# SOS_receiver.net
KiCad netlist of a schematic drawn in EasyEDA
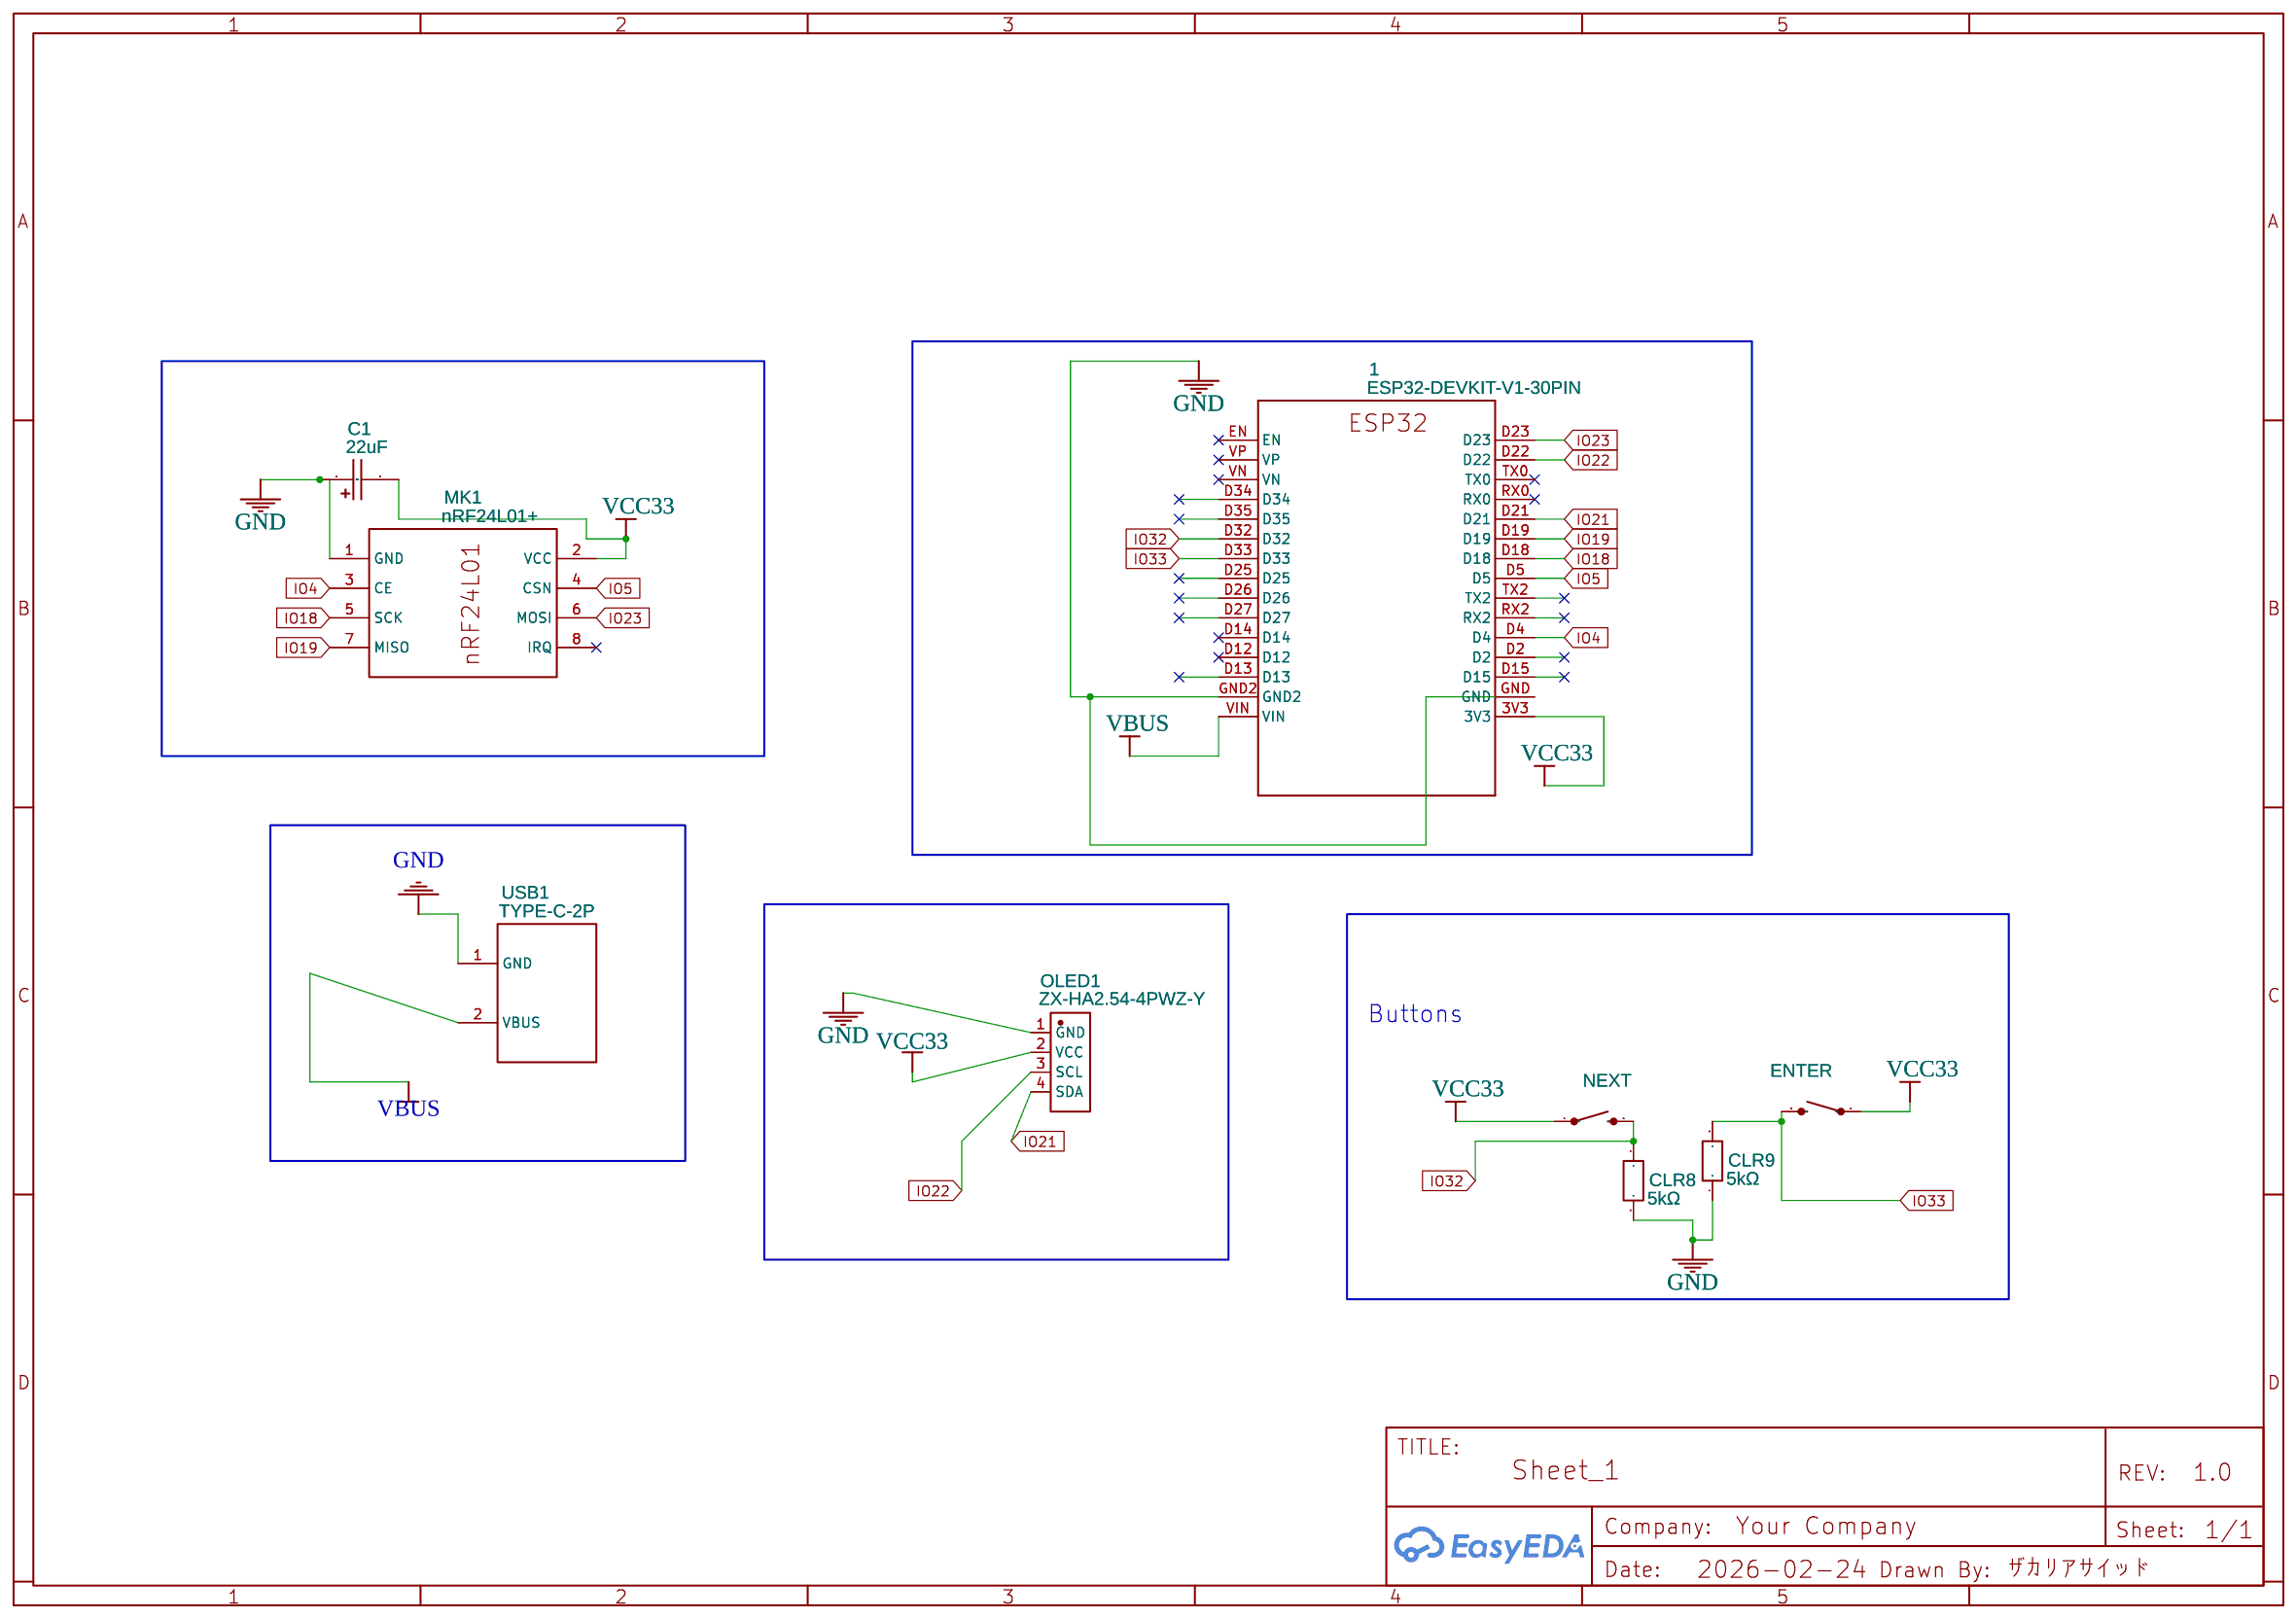
[diagram p0: schematic sheet]

(export (version "E")
  (design (tool "Eeschema 10.0.6"))
  (components
    (comp (ref "1") (value "ESP32-DEVKIT-V1-30PIN") (libsource (lib "") (part "ESP32-DEVKIT-V1-30PIN")))
    (comp (ref "C1")
      (value "22uF")
      (fields (field (name "Manufacturer Part") "UES1V220MPM1TD") (field (name "Manufacturer") "Nichicon"))
      (libsource (lib "") (part "22uF_16V"))
    )
    (comp (ref "CLR8") (value "5kΩ") (libsource (lib "") (part "R_AXIAL-0.4_EU_1")))
    (comp (ref "CLR9") (value "5kΩ") (libsource (lib "") (part "R_AXIAL-0.4_EU")))
    (comp (ref "ENTER") (value "SWITCHES_PTH_EZ") (libsource (lib "") (part "SWITCHES_PTH_EZ_1")))
    (comp (ref "MK1") (value "nRF24L01+") (libsource (lib "") (part "nRF24L01+")))
    (comp (ref "NEXT") (value "SWITCHES_PTH_EZ") (libsource (lib "") (part "SWITCHES_PTH_EZ")))
    (comp (ref "OLED1")
      (value "ZX-HA2.54-4PWZ-Y")
      (fields (field (name "Manufacturer") "Megastar(兆星)"))
      (libsource (lib "") (part "ZX-HA2.54-4PWZ-Y"))
    )
    (comp (ref "USB1") (value "TYPE-C-2P") (libsource (lib "") (part "TYPE-C-2P")))
  )
  (nets
    (net (code "1") (name "GND") (class "Default")
      (node (ref "1") (pin "GND") (pinfunction "GND_GND") (pintype "unspecified"))
      (node (ref "1") (pin "GND2") (pinfunction "GND2_GND2") (pintype "unspecified"))
      (node (ref "C1") (pin "1") (pinfunction "1_1") (pintype "unspecified"))
      (node (ref "CLR8") (pin "2") (pinfunction "2_2") (pintype "unspecified"))
      (node (ref "CLR9") (pin "1") (pinfunction "1_1") (pintype "unspecified"))
      (node (ref "MK1") (pin "1") (pinfunction "GND_1") (pintype "unspecified"))
      (node (ref "OLED1") (pin "1") (pinfunction "GND_1") (pintype "unspecified"))
      (node (ref "USB1") (pin "1") (pinfunction "GND_1") (pintype "unspecified"))
    )
    (net (code "2") (name "IO4") (class "Default")
      (node (ref "1") (pin "D4") (pinfunction "D4_D4") (pintype "unspecified"))
      (node (ref "MK1") (pin "3") (pinfunction "CE_3") (pintype "unspecified"))
    )
    (net (code "3") (name "IO5") (class "Default")
      (node (ref "1") (pin "D5") (pinfunction "D5_D5") (pintype "unspecified"))
      (node (ref "MK1") (pin "4") (pinfunction "CSN_4") (pintype "unspecified"))
    )
    (net (code "4") (name "IO18") (class "Default")
      (node (ref "1") (pin "D18") (pinfunction "D18_D18") (pintype "unspecified"))
      (node (ref "MK1") (pin "5") (pinfunction "SCK_5") (pintype "unspecified"))
    )
    (net (code "5") (name "IO19") (class "Default")
      (node (ref "1") (pin "D19") (pinfunction "D19_D19") (pintype "unspecified"))
      (node (ref "MK1") (pin "7") (pinfunction "MISO_7") (pintype "unspecified"))
    )
    (net (code "6") (name "IO21") (class "Default")
      (node (ref "1") (pin "D21") (pinfunction "D21_D21") (pintype "unspecified"))
      (node (ref "OLED1") (pin "4") (pinfunction "SDA_4") (pintype "unspecified"))
    )
    (net (code "7") (name "IO22") (class "Default")
      (node (ref "1") (pin "D22") (pinfunction "D22_D22") (pintype "unspecified"))
      (node (ref "OLED1") (pin "3") (pinfunction "SCL_3") (pintype "unspecified"))
    )
    (net (code "8") (name "IO23") (class "Default")
      (node (ref "1") (pin "D23") (pinfunction "D23_D23") (pintype "unspecified"))
      (node (ref "MK1") (pin "6") (pinfunction "MOSI_6") (pintype "unspecified"))
    )
    (net (code "9") (name "IO32") (class "Default")
      (node (ref "1") (pin "D32") (pinfunction "D32_D32") (pintype "unspecified"))
      (node (ref "CLR8") (pin "1") (pinfunction "1_1") (pintype "unspecified"))
      (node (ref "NEXT") (pin "3") (pinfunction "2_3") (pintype "unspecified"))
    )
    (net (code "10") (name "IO33") (class "Default")
      (node (ref "1") (pin "D33") (pinfunction "D33_D33") (pintype "unspecified"))
      (node (ref "CLR9") (pin "2") (pinfunction "2_2") (pintype "unspecified"))
      (node (ref "ENTER") (pin "3") (pinfunction "2_3") (pintype "unspecified"))
    )
    (net (code "11") (name "VBUS") (class "Default")
      (node (ref "1") (pin "VIN") (pinfunction "VIN_VIN") (pintype "unspecified"))
      (node (ref "USB1") (pin "2") (pinfunction "VBUS_2") (pintype "unspecified"))
    )
    (net (code "12") (name "VCC33") (class "Default")
      (node (ref "1") (pin "3V3") (pinfunction "3V3_3V3") (pintype "unspecified"))
      (node (ref "C1") (pin "2") (pinfunction "2_2") (pintype "unspecified"))
      (node (ref "ENTER") (pin "1") (pinfunction "1_1") (pintype "unspecified"))
      (node (ref "MK1") (pin "2") (pinfunction "VCC_2") (pintype "unspecified"))
      (node (ref "NEXT") (pin "1") (pinfunction "1_1") (pintype "unspecified"))
      (node (ref "OLED1") (pin "2") (pinfunction "VCC_2") (pintype "unspecified"))
    )
    (net (code "13") (name "unconnected-(1-PadD2)") (class "Default")
      (node (ref "1") (pin "D2") (pinfunction "D2_D2") (pintype "unspecified+no_connect"))
    )
    (net (code "14") (name "unconnected-(1-PadD12)") (class "Default")
      (node (ref "1") (pin "D12") (pinfunction "D12_D12") (pintype "unspecified+no_connect"))
    )
    (net (code "15") (name "unconnected-(1-PadD13)") (class "Default")
      (node (ref "1") (pin "D13") (pinfunction "D13_D13") (pintype "unspecified+no_connect"))
    )
    (net (code "16") (name "unconnected-(1-PadD14)") (class "Default")
      (node (ref "1") (pin "D14") (pinfunction "D14_D14") (pintype "unspecified+no_connect"))
    )
    (net (code "17") (name "unconnected-(1-PadD15)") (class "Default")
      (node (ref "1") (pin "D15") (pinfunction "D15_D15") (pintype "unspecified+no_connect"))
    )
    (net (code "18") (name "unconnected-(1-PadD25)") (class "Default")
      (node (ref "1") (pin "D25") (pinfunction "D25_D25") (pintype "unspecified+no_connect"))
    )
    (net (code "19") (name "unconnected-(1-PadD26)") (class "Default")
      (node (ref "1") (pin "D26") (pinfunction "D26_D26") (pintype "unspecified+no_connect"))
    )
    (net (code "20") (name "unconnected-(1-PadD27)") (class "Default")
      (node (ref "1") (pin "D27") (pinfunction "D27_D27") (pintype "unspecified+no_connect"))
    )
    (net (code "21") (name "unconnected-(1-PadD34)") (class "Default")
      (node (ref "1") (pin "D34") (pinfunction "D34_D34") (pintype "unspecified+no_connect"))
    )
    (net (code "22") (name "unconnected-(1-PadD35)") (class "Default")
      (node (ref "1") (pin "D35") (pinfunction "D35_D35") (pintype "unspecified+no_connect"))
    )
    (net (code "23") (name "unconnected-(1-PadEN)") (class "Default")
      (node (ref "1") (pin "EN") (pinfunction "EN_EN") (pintype "unspecified+no_connect"))
    )
    (net (code "24") (name "unconnected-(1-PadRX0)") (class "Default")
      (node (ref "1") (pin "RX0") (pinfunction "RX0_RX0") (pintype "unspecified+no_connect"))
    )
    (net (code "25") (name "unconnected-(1-PadRX2)") (class "Default")
      (node (ref "1") (pin "RX2") (pinfunction "RX2_RX2") (pintype "unspecified+no_connect"))
    )
    (net (code "26") (name "unconnected-(1-PadTX0)") (class "Default")
      (node (ref "1") (pin "TX0") (pinfunction "TX0_TX0") (pintype "unspecified+no_connect"))
    )
    (net (code "27") (name "unconnected-(1-PadTX2)") (class "Default")
      (node (ref "1") (pin "TX2") (pinfunction "TX2_TX2") (pintype "unspecified+no_connect"))
    )
    (net (code "28") (name "unconnected-(1-PadVN)") (class "Default")
      (node (ref "1") (pin "VN") (pinfunction "VN_VN") (pintype "unspecified+no_connect"))
    )
    (net (code "29") (name "unconnected-(1-PadVP)") (class "Default")
      (node (ref "1") (pin "VP") (pinfunction "VP_VP") (pintype "unspecified+no_connect"))
    )
    (net (code "30") (name "unconnected-(MK1-IRQ-Pad8)") (class "Default")
      (node (ref "MK1") (pin "8") (pinfunction "IRQ_8") (pintype "unspecified+no_connect"))
    )
  )
)
